# STM32F407_MCU.net
KiCad netlist of a schematic drawn in Altium Designer
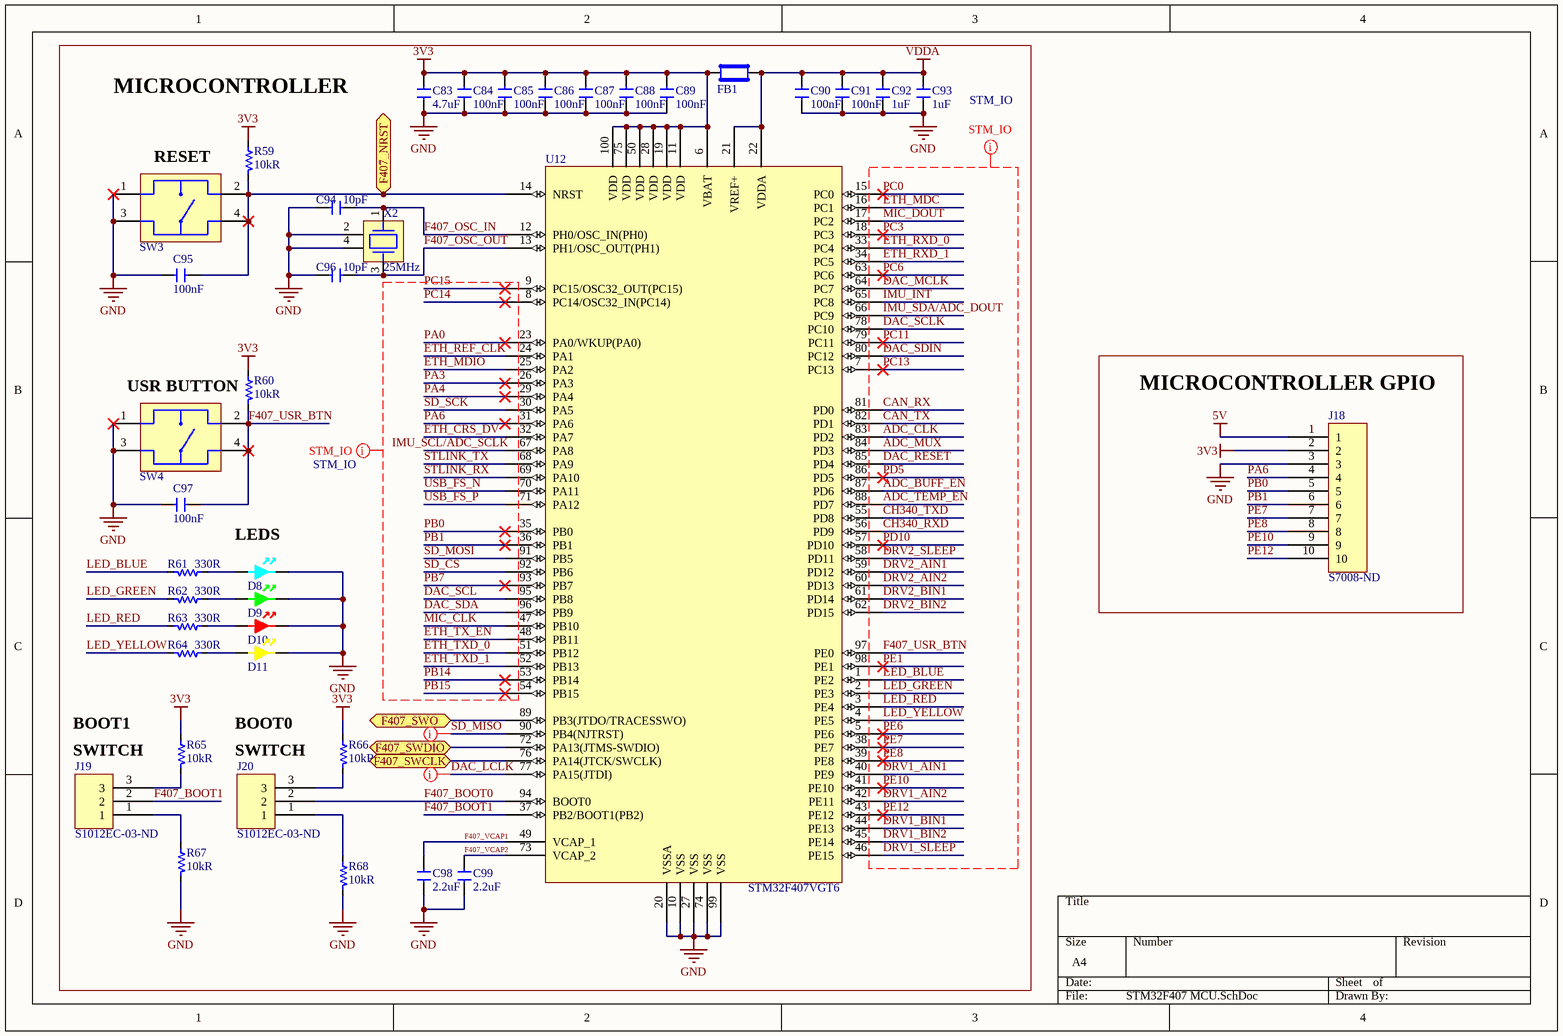
[diagram p0: STM32F407 MCU.SchDoc]

(export (version "E")
  (design (tool "Eeschema 10.0.6"))
  (components
    (comp (ref "C83")
      (value "CAP_4.7uF_%10_0805_25V_X7R_CER")
      (footprint "0805_CAP")
      (description "Cap 4.7UF 25VDC X7R 10% SMD 0805 Embossed Tape")
      (fields
        (field (name "MANUFACTURER") "Murata")
        (field (name "MANUFACTURER PART NUMBER") "GRM21BZ71E475KE15L")
        (field (name "CAPACITANCE") "4.7uF")
      )
      (libsource (lib "Main Schematic Library") (part "CAP_4.7uF_%10_0805_25V_X7R_CER"))
    )
    (comp (ref "C84")
      (value "CAP_0.1uF_%20_50V_0805_X7R_CER")
      (footprint "0805_CAP")
      (description "Cap Ceramic 0.1uF 50V X7R 20% SMD 0805 125C Paper T/R")
      (fields
        (field (name "MANUFACTURER") "KEMET")
        (field (name "MANUFACTURER PART NUMBER") "C0805C104M5RACTU")
        (field (name "CAPACITANCE") "100nF")
      )
      (libsource (lib "Main Schematic Library") (part "CAP_0.1uF_%20_50V_0805_X7R_CER"))
    )
    (comp (ref "C85")
      (value "CAP_0.1uF_%20_50V_0805_X7R_CER")
      (footprint "0805_CAP")
      (description "Cap Ceramic 0.1uF 50V X7R 20% SMD 0805 125C Paper T/R")
      (fields
        (field (name "MANUFACTURER") "KEMET")
        (field (name "MANUFACTURER PART NUMBER") "C0805C104M5RACTU")
        (field (name "CAPACITANCE") "100nF")
      )
      (libsource (lib "Main Schematic Library") (part "CAP_0.1uF_%20_50V_0805_X7R_CER"))
    )
    (comp (ref "C86")
      (value "CAP_0.1uF_%20_50V_0805_X7R_CER")
      (footprint "0805_CAP")
      (description "Cap Ceramic 0.1uF 50V X7R 20% SMD 0805 125C Paper T/R")
      (fields
        (field (name "MANUFACTURER") "KEMET")
        (field (name "MANUFACTURER PART NUMBER") "C0805C104M5RACTU")
        (field (name "CAPACITANCE") "100nF")
      )
      (libsource (lib "Main Schematic Library") (part "CAP_0.1uF_%20_50V_0805_X7R_CER"))
    )
    (comp (ref "C87")
      (value "CAP_0.1uF_%20_50V_0805_X7R_CER")
      (footprint "0805_CAP")
      (description "Cap Ceramic 0.1uF 50V X7R 20% SMD 0805 125C Paper T/R")
      (fields
        (field (name "MANUFACTURER") "KEMET")
        (field (name "MANUFACTURER PART NUMBER") "C0805C104M5RACTU")
        (field (name "CAPACITANCE") "100nF")
      )
      (libsource (lib "Main Schematic Library") (part "CAP_0.1uF_%20_50V_0805_X7R_CER"))
    )
    (comp (ref "C88")
      (value "CAP_0.1uF_%20_50V_0805_X7R_CER")
      (footprint "0805_CAP")
      (description "Cap Ceramic 0.1uF 50V X7R 20% SMD 0805 125C Paper T/R")
      (fields
        (field (name "MANUFACTURER") "KEMET")
        (field (name "MANUFACTURER PART NUMBER") "C0805C104M5RACTU")
        (field (name "CAPACITANCE") "100nF")
      )
      (libsource (lib "Main Schematic Library") (part "CAP_0.1uF_%20_50V_0805_X7R_CER"))
    )
    (comp (ref "C89")
      (value "CAP_0.1uF_%20_50V_0805_X7R_CER")
      (footprint "0805_CAP")
      (description "Cap Ceramic 0.1uF 50V X7R 20% SMD 0805 125C Paper T/R")
      (fields
        (field (name "MANUFACTURER") "KEMET")
        (field (name "MANUFACTURER PART NUMBER") "C0805C104M5RACTU")
        (field (name "CAPACITANCE") "100nF")
      )
      (libsource (lib "Main Schematic Library") (part "CAP_0.1uF_%20_50V_0805_X7R_CER"))
    )
    (comp (ref "C90")
      (value "CAP_0.1uF_%20_50V_0805_X7R_CER")
      (footprint "0805_CAP")
      (description "Cap Ceramic 0.1uF 50V X7R 20% SMD 0805 125C Paper T/R")
      (fields
        (field (name "MANUFACTURER") "KEMET")
        (field (name "MANUFACTURER PART NUMBER") "C0805C104M5RACTU")
        (field (name "CAPACITANCE") "100nF")
      )
      (libsource (lib "Main Schematic Library") (part "CAP_0.1uF_%20_50V_0805_X7R_CER"))
    )
    (comp (ref "C91")
      (value "CAP_0.1uF_%20_50V_0805_X7R_CER")
      (footprint "0805_CAP")
      (description "Cap Ceramic 0.1uF 50V X7R 20% SMD 0805 125C Paper T/R")
      (fields
        (field (name "MANUFACTURER") "KEMET")
        (field (name "MANUFACTURER PART NUMBER") "C0805C104M5RACTU")
        (field (name "CAPACITANCE") "100nF")
      )
      (libsource (lib "Main Schematic Library") (part "CAP_0.1uF_%20_50V_0805_X7R_CER"))
    )
    (comp (ref "C92")
      (value "1uF")
      (footprint "0805_CAP")
      (description "陶瓷电容 1uF(105) 1uF ±10% 25V 0805")
      (fields
        (field (name "MANUFACTURER") "Samsung")
        (field (name "MANUFACTURER PART NUMBER") "CL21B105KAFNNNG")
      )
      (libsource (lib "Main Schematic Library") (part "CAP_1uF_%10_25V_0805_X7R_CER"))
    )
    (comp (ref "C93")
      (value "1uF")
      (footprint "0805_CAP")
      (description "陶瓷电容 1uF(105) 1uF ±10% 25V 0805")
      (fields
        (field (name "MANUFACTURER") "Samsung")
        (field (name "MANUFACTURER PART NUMBER") "CL21B105KAFNNNG")
      )
      (libsource (lib "Main Schematic Library") (part "CAP_1uF_%10_25V_0805_X7R_CER"))
    )
    (comp (ref "C94")
      (value "CAP_10pF_%10_0805_50V_C0G/NPO_CER")
      (footprint "0805_CAP")
      (description "Surface Mount Ceramic Multilayer Capacitor 10pF 10% C0G 50V 0805 Paper T/R")
      (fields
        (field (name "MANUFACTURER") "Yageo")
        (field (name "MANUFACTURER PART NUMBER") "CC0805KRNPO9BN100")
        (field (name "CAPACITANCE") "10pF")
      )
      (libsource (lib "Main Schematic Library") (part "CAP_10pF_%10_0805_50V_C0G/NPO_CER"))
    )
    (comp (ref "C95")
      (value "CAP_100nF_50V_0805_C0G_CER")
      (footprint "0805_CAP")
      (description "Cap Ceramic 0.1uF 50V X7R 20% SMD 0805 125C Paper T/R")
      (fields
        (field (name "MANUFACTURER") "KEMET")
        (field (name "MANUFACTURER PART NUMBER") "C0805C104M5RACTU")
        (field (name "CAPACITANCE") "100nF")
      )
      (libsource (lib "Main Schematic Library") (part "CAP_100nF_50V_0805_C0G_CER"))
    )
    (comp (ref "C96")
      (value "CAP_10pF_%10_0805_50V_C0G/NPO_CER")
      (footprint "0805_CAP")
      (description "Surface Mount Ceramic Multilayer Capacitor 10pF 10% C0G 50V 0805 Paper T/R")
      (fields
        (field (name "MANUFACTURER") "Yageo")
        (field (name "MANUFACTURER PART NUMBER") "CC0805KRNPO9BN100")
        (field (name "CAPACITANCE") "10pF")
      )
      (libsource (lib "Main Schematic Library") (part "CAP_10pF_%10_0805_50V_C0G/NPO_CER"))
    )
    (comp (ref "C97")
      (value "CAP_100nF_50V_0805_C0G_CER")
      (footprint "0805_CAP")
      (description "Cap Ceramic 0.1uF 50V X7R 20% SMD 0805 125C Paper T/R")
      (fields
        (field (name "MANUFACTURER") "KEMET")
        (field (name "MANUFACTURER PART NUMBER") "C0805C104M5RACTU")
        (field (name "CAPACITANCE") "100nF")
      )
      (libsource (lib "Main Schematic Library") (part "CAP_100nF_50V_0805_C0G_CER"))
    )
    (comp (ref "C98")
      (value "2.2uF")
      (footprint "0805_CAP")
      (description "CAP CER 2.2UF 25V X5R 0805")
      (fields
        (field (name "MANUFACTURER") "Samsung")
        (field (name "MANUFACTURER PART NUMBER") "CL21A225KAFNNNE")
      )
      (libsource (lib "Main Schematic Library") (part "CAP_2.2uF_%10_25V_0805_X5R_CER"))
    )
    (comp (ref "C99")
      (value "2.2uF")
      (footprint "0805_CAP")
      (description "CAP CER 2.2UF 25V X5R 0805")
      (fields
        (field (name "MANUFACTURER") "Samsung")
        (field (name "MANUFACTURER PART NUMBER") "CL21A225KAFNNNE")
      )
      (libsource (lib "Main Schematic Library") (part "CAP_2.2uF_%10_25V_0805_X5R_CER"))
    )
    (comp (ref "D8")
      (value "Blue")
      (footprint "DIOC2114X07N-0805-LED-BLUE")
      (description "Blue 0805 140° 112 mcd Clear 3.3 V Surface Mount LED")
      (fields
        (field (name "MANUFACTURER") "Everlight")
        (field (name "MANUFACTURER PART NUMBER") "EAST2012BA2")
      )
      (libsource (lib "Main Schematic Library") (part "LED_BLUE CLEAR_2SMD/0805"))
    )
    (comp (ref "D9")
      (value "Green")
      (footprint "DIOC2114X07N-0805-LED-GREEN")
      (description "Led Green Clear 2SMD")
      (fields
        (field (name "MANUFACTURER") "Everlight")
        (field (name "MANUFACTURER PART NUMBER") "EAST2012GA5")
      )
      (libsource (lib "Main Schematic Library") (part "LED_GREEN CLEAR_2SMD/0805"))
    )
    (comp (ref "D10")
      (value "Red")
      (footprint "DIOC2114X07N-0805-LED-RED")
      (description "Led Red Clear 2SMD")
      (fields
        (field (name "MANUFACTURER") "Everlight")
        (field (name "MANUFACTURER PART NUMBER") "EAST2012RA1")
      )
      (libsource (lib "Main Schematic Library") (part "LED_RED CLEAR_2SMD/0805"))
    )
    (comp (ref "D11")
      (value "Yellow")
      (footprint "DIOC2114X07N-0805-LED-YELLOW")
      (description "Led Yellow Clear 2SMD")
      (fields
        (field (name "MANUFACTURER") "Everlight")
        (field (name "MANUFACTURER PART NUMBER") "EAST2012YA2")
      )
      (libsource (lib "Main Schematic Library") (part "LED_YELLOW CLEAR_2SMD/0805"))
    )
    (comp (ref "FB1")
      (value "FERRITE BEAD_330 OHM_70 mOHM DCR_0805_1LN")
      (footprint "0805_FB")
      (description "0805 330Ω ±25% DCR=0.07Ω 1.5A 应用：电源线")
      (fields (field (name "MANUFACTURER") "Murata") (field (name "TOLERANCE") "25%"))
      (libsource (lib "Main Schematic Library") (part "FERRITE BEAD_330 OHM_70 mOHM DCR_0805_1LN"))
    )
    (comp (ref "J18")
      (value "1x10-Male Header")
      (footprint "DIP_1X10_FEMALE_HEADER_2.54_PITCH")
      (description "10 Position Single Row 2.54 mm Pitch Vertical Through Hole Socket Header")
      (fields
        (field (name "MANUFACTURER") "Sullins")
        (field (name "MANUFACTURER PART NUMBER") "PPTC101LFBN-RC")
        (field (name "SUPPLIER PART NUMBER 1") "S7008-ND")
      )
      (libsource (lib "Main Schematic Library") (part "CONN_1x10_2.54m_Female Header"))
    )
    (comp (ref "J19")
      (value "CONN_1X3_2.54mm_Male Header")
      (footprint "DIP_1X3_MALE_HEADER_2.54_PITCH")
      (description "Conn Header Vert 3POS 2.54MM")
      (fields
        (field (name "MANUFACTURER") "Sullins")
        (field (name "MANUFACTURER PART NUMBER") "PREC003SAAN-RC")
        (field (name "SUPPLIER PART NUMBER 1") "S1012EC-03-ND")
      )
      (libsource (lib "Main Schematic Library") (part "CONN_1X3_2.54mm_Male Header"))
    )
    (comp (ref "J20")
      (value "CONN_1X3_2.54mm_Male Header")
      (footprint "DIP_1X3_MALE_HEADER_2.54_PITCH")
      (description "Conn Header Vert 3POS 2.54MM")
      (fields
        (field (name "MANUFACTURER") "Sullins")
        (field (name "MANUFACTURER PART NUMBER") "PREC003SAAN-RC")
        (field (name "SUPPLIER PART NUMBER 1") "S1012EC-03-ND")
      )
      (libsource (lib "Main Schematic Library") (part "CONN_1X3_2.54mm_Male Header"))
    )
    (comp (ref "R59")
      (value "10k Ohms")
      (footprint "0805_RES")
      (description "Res SMD 0805 10K 1% 0.125W T.C.100PPM")
      (fields
        (field (name "MANUFACTURER") "TDK")
        (field (name "MANUFACTURER PART NUMBER") "C2012X7R1H104K085AA")
        (field (name "RESISTANCE") "10kR")
      )
      (libsource (lib "Main Schematic Library") (part "RES_10K OHM_%1_0805_1/8W"))
    )
    (comp (ref "R60")
      (value "10k Ohms")
      (footprint "0805_RES")
      (description "Res SMD 0805 10K 1% 0.125W T.C.100PPM")
      (fields
        (field (name "MANUFACTURER") "TDK")
        (field (name "MANUFACTURER PART NUMBER") "C2012X7R1H104K085AA")
        (field (name "RESISTANCE") "10kR")
      )
      (libsource (lib "Main Schematic Library") (part "RES_10K OHM_%1_0805_1/8W"))
    )
    (comp (ref "R61")
      (value "RES_330 OHM_5%_0805_1/8W")
      (footprint "0805_RES")
      (description "Res Thick Film 0805 330 Ohm 5% 0.125W(1/8W) ±100ppm/C Pad SMD Automotive T/R")
      (fields
        (field (name "MANUFACTURER") "TE Connectivity")
        (field (name "MANUFACTURER PART NUMBER") "CRGCQ0805J330R")
        (field (name "RESISTANCE") "330R")
      )
      (libsource (lib "Main Schematic Library") (part "RES_330 OHM_5%_0805_1/8W"))
    )
    (comp (ref "R62")
      (value "RES_330 OHM_5%_0805_1/8W")
      (footprint "0805_RES")
      (description "Res Thick Film 0805 330 Ohm 5% 0.125W(1/8W) ±100ppm/C Pad SMD Automotive T/R")
      (fields
        (field (name "MANUFACTURER") "TE Connectivity")
        (field (name "MANUFACTURER PART NUMBER") "CRGCQ0805J330R")
        (field (name "RESISTANCE") "330R")
      )
      (libsource (lib "Main Schematic Library") (part "RES_330 OHM_5%_0805_1/8W"))
    )
    (comp (ref "R63")
      (value "RES_330 OHM_5%_0805_1/8W")
      (footprint "0805_RES")
      (description "Res Thick Film 0805 330 Ohm 5% 0.125W(1/8W) ±100ppm/C Pad SMD Automotive T/R")
      (fields
        (field (name "MANUFACTURER") "TE Connectivity")
        (field (name "MANUFACTURER PART NUMBER") "CRGCQ0805J330R")
        (field (name "RESISTANCE") "330R")
      )
      (libsource (lib "Main Schematic Library") (part "RES_330 OHM_5%_0805_1/8W"))
    )
    (comp (ref "R64")
      (value "RES_330 OHM_5%_0805_1/8W")
      (footprint "0805_RES")
      (description "Res Thick Film 0805 330 Ohm 5% 0.125W(1/8W) ±100ppm/C Pad SMD Automotive T/R")
      (fields
        (field (name "MANUFACTURER") "TE Connectivity")
        (field (name "MANUFACTURER PART NUMBER") "CRGCQ0805J330R")
        (field (name "RESISTANCE") "330R")
      )
      (libsource (lib "Main Schematic Library") (part "RES_330 OHM_5%_0805_1/8W"))
    )
    (comp (ref "R65")
      (value "10k Ohms")
      (footprint "0805_RES")
      (description "Res SMD 0805 10K 1% 0.125W T.C.100PPM")
      (fields
        (field (name "MANUFACTURER") "TDK")
        (field (name "MANUFACTURER PART NUMBER") "C2012X7R1H104K085AA")
        (field (name "RESISTANCE") "10kR")
      )
      (libsource (lib "Main Schematic Library") (part "RES_10K OHM_%1_0805_1/8W"))
    )
    (comp (ref "R66")
      (value "10k Ohms")
      (footprint "0805_RES")
      (description "Res SMD 0805 10K 1% 0.125W T.C.100PPM")
      (fields
        (field (name "MANUFACTURER") "TDK")
        (field (name "MANUFACTURER PART NUMBER") "C2012X7R1H104K085AA")
        (field (name "RESISTANCE") "10kR")
      )
      (libsource (lib "Main Schematic Library") (part "RES_10K OHM_%1_0805_1/8W"))
    )
    (comp (ref "R67")
      (value "10k Ohms")
      (footprint "0805_RES")
      (description "Res SMD 0805 10K 1% 0.125W T.C.100PPM")
      (fields
        (field (name "MANUFACTURER") "TDK")
        (field (name "MANUFACTURER PART NUMBER") "C2012X7R1H104K085AA")
        (field (name "RESISTANCE") "10kR")
      )
      (libsource (lib "Main Schematic Library") (part "RES_10K OHM_%1_0805_1/8W"))
    )
    (comp (ref "R68")
      (value "10k Ohms")
      (footprint "0805_RES")
      (description "Res SMD 0805 10K 1% 0.125W T.C.100PPM")
      (fields
        (field (name "MANUFACTURER") "TDK")
        (field (name "MANUFACTURER PART NUMBER") "C2012X7R1H104K085AA")
        (field (name "RESISTANCE") "10kR")
      )
      (libsource (lib "Main Schematic Library") (part "RES_10K OHM_%1_0805_1/8W"))
    )
    (comp (ref "SW3")
      (value "SWITCH_TACTILE_SPST-NO_0.05A_12V")
      (footprint "TACT_SWITCH_6MMX6MM")
      (description "Switch Tactile N.O. SPST Round Button Gull Wing 0.05A 12VDC 100000Cycles 1.27N SMD T/R")
      (fields
        (field (name "MANUFACTURER") "ITT C&K")
        (field (name "MANUFACTURER PART NUMBER") "PTS645SL43SMTR92LFS")
      )
      (libsource (lib "Main Schematic Library") (part "SWITCH_TACTILE_SPST-NO_0.05A_12V"))
    )
    (comp (ref "SW4")
      (value "SWITCH_TACTILE_SPST-NO_0.05A_12V")
      (footprint "TACT_SWITCH_6MMX6MM")
      (description "Switch Tactile N.O. SPST Round Button Gull Wing 0.05A 12VDC 100000Cycles 1.27N SMD T/R")
      (fields
        (field (name "MANUFACTURER") "ITT C&K")
        (field (name "MANUFACTURER PART NUMBER") "PTS645SL43SMTR92LFS")
      )
      (libsource (lib "Main Schematic Library") (part "SWITCH_TACTILE_SPST-NO_0.05A_12V"))
    )
    (comp (ref "U12")
      (value "STM32F407VGT6")
      (footprint "STM32F407_LQFP50P1600X1600X160-100N")
      (description "MCU 32-bit STM32F ARM Cortex M4F RISC 1024KB Flash 2.5V/3.3V 100-Pin LQFP Tray")
      (fields (field (name "MANUFACTURER") "STMicroelectronics"))
      (libsource (lib "Main Schematic Library") (part "IC_MCU_STM32F407VGT6"))
    )
    (comp (ref "X2")
      (value "25MHz")
      (footprint "4-SMD-ABM8G-25.000MHZ-4Y-T3")
      (description "Crystal 25MHz ±30ppm (Tol) ±30ppm (Stability) 10pF FUND 60Ohm 4-Pin Ultra Mini-CSMD T/R")
      (fields
        (field (name "MANUFACTURER") "Abracon")
        (field (name "MANUFACTURER PART NUMBER") "ABM8G-25.000MHZ-4Y-T3")
      )
      (libsource (lib "Main Schematic Library") (part "CRYSTAL_25.0000MHZ_10PF_SMD"))
    )
  )
  (nets
    (net (code "1") (name "/ADC_BUFF_EN") (class "Default")
      (node (ref "U12") (pin "87") (pinfunction "PD6_87") (pintype "bidirectional"))
    )
    (net (code "2") (name "/ADC_CLK") (class "Default")
      (node (ref "U12") (pin "83") (pinfunction "PD2_83") (pintype "bidirectional"))
    )
    (net (code "3") (name "/ADC_MUX") (class "Default")
      (node (ref "U12") (pin "84") (pinfunction "PD3_84") (pintype "bidirectional"))
    )
    (net (code "4") (name "/ADC_TEMP_EN") (class "Default")
      (node (ref "U12") (pin "88") (pinfunction "PD7_88") (pintype "bidirectional"))
    )
    (net (code "5") (name "/CAN_RX") (class "Default")
      (node (ref "U12") (pin "81") (pinfunction "PD0_81") (pintype "bidirectional"))
    )
    (net (code "6") (name "/CAN_TX") (class "Default")
      (node (ref "U12") (pin "82") (pinfunction "PD1_82") (pintype "bidirectional"))
    )
    (net (code "7") (name "/CH340_RXD") (class "Default")
      (node (ref "U12") (pin "56") (pinfunction "PD9_56") (pintype "bidirectional"))
    )
    (net (code "8") (name "/CH340_TXD") (class "Default")
      (node (ref "U12") (pin "55") (pinfunction "PD8_55") (pintype "bidirectional"))
    )
    (net (code "9") (name "/DAC_LCLK") (class "Default")
      (node (ref "U12") (pin "77") (pinfunction "PA15(JTDI)_77") (pintype "bidirectional"))
    )
    (net (code "10") (name "/DAC_MCLK") (class "Default")
      (node (ref "U12") (pin "64") (pinfunction "PC7_64") (pintype "bidirectional"))
    )
    (net (code "11") (name "/DAC_RESET") (class "Default")
      (node (ref "U12") (pin "85") (pinfunction "PD4_85") (pintype "bidirectional"))
    )
    (net (code "12") (name "/DAC_SCL") (class "Default")
      (node (ref "U12") (pin "95") (pinfunction "PB8_95") (pintype "bidirectional"))
    )
    (net (code "13") (name "/DAC_SCLK") (class "Default")
      (node (ref "U12") (pin "78") (pinfunction "PC10_78") (pintype "bidirectional"))
    )
    (net (code "14") (name "/DAC_SDA") (class "Default")
      (node (ref "U12") (pin "96") (pinfunction "PB9_96") (pintype "bidirectional"))
    )
    (net (code "15") (name "/DAC_SDIN") (class "Default")
      (node (ref "U12") (pin "80") (pinfunction "PC12_80") (pintype "bidirectional"))
    )
    (net (code "16") (name "/DRV1_AIN1") (class "Default")
      (node (ref "U12") (pin "40") (pinfunction "PE9_40") (pintype "bidirectional"))
    )
    (net (code "17") (name "/DRV1_AIN2") (class "Default")
      (node (ref "U12") (pin "42") (pinfunction "PE11_42") (pintype "bidirectional"))
    )
    (net (code "18") (name "/DRV1_BIN1") (class "Default")
      (node (ref "U12") (pin "44") (pinfunction "PE13_44") (pintype "bidirectional"))
    )
    (net (code "19") (name "/DRV1_BIN2") (class "Default")
      (node (ref "U12") (pin "45") (pinfunction "PE14_45") (pintype "bidirectional"))
    )
    (net (code "20") (name "/DRV1_SLEEP") (class "Default")
      (node (ref "U12") (pin "46") (pinfunction "PE15_46") (pintype "bidirectional"))
    )
    (net (code "21") (name "/DRV2_AIN1") (class "Default")
      (node (ref "U12") (pin "59") (pinfunction "PD12_59") (pintype "bidirectional"))
    )
    (net (code "22") (name "/DRV2_AIN2") (class "Default")
      (node (ref "U12") (pin "60") (pinfunction "PD13_60") (pintype "bidirectional"))
    )
    (net (code "23") (name "/DRV2_BIN1") (class "Default")
      (node (ref "U12") (pin "61") (pinfunction "PD14_61") (pintype "bidirectional"))
    )
    (net (code "24") (name "/DRV2_BIN2") (class "Default")
      (node (ref "U12") (pin "62") (pinfunction "PD15_62") (pintype "bidirectional"))
    )
    (net (code "25") (name "/DRV2_SLEEP") (class "Default")
      (node (ref "U12") (pin "58") (pinfunction "PD11_58") (pintype "bidirectional"))
    )
    (net (code "26") (name "/ETH_CRS_DV") (class "Default")
      (node (ref "U12") (pin "32") (pinfunction "PA7_32") (pintype "bidirectional"))
    )
    (net (code "27") (name "/ETH_MDC") (class "Default")
      (node (ref "U12") (pin "16") (pinfunction "PC1_16") (pintype "bidirectional"))
    )
    (net (code "28") (name "/ETH_MDIO") (class "Default")
      (node (ref "U12") (pin "25") (pinfunction "PA2_25") (pintype "bidirectional"))
    )
    (net (code "29") (name "/ETH_REF_CLK") (class "Default")
      (node (ref "U12") (pin "24") (pinfunction "PA1_24") (pintype "bidirectional"))
    )
    (net (code "30") (name "/ETH_RXD_0") (class "Default")
      (node (ref "U12") (pin "33") (pinfunction "PC4_33") (pintype "bidirectional"))
    )
    (net (code "31") (name "/ETH_RXD_1") (class "Default")
      (node (ref "U12") (pin "34") (pinfunction "PC5_34") (pintype "bidirectional"))
    )
    (net (code "32") (name "/ETH_TXD_0") (class "Default")
      (node (ref "U12") (pin "51") (pinfunction "PB12_51") (pintype "bidirectional"))
    )
    (net (code "33") (name "/ETH_TXD_1") (class "Default")
      (node (ref "U12") (pin "52") (pinfunction "PB13_52") (pintype "bidirectional"))
    )
    (net (code "34") (name "/ETH_TX_EN") (class "Default")
      (node (ref "U12") (pin "48") (pinfunction "PB11_48") (pintype "bidirectional"))
    )
    (net (code "35") (name "/F407_BOOT0") (class "Default")
      (node (ref "J20") (pin "2") (pinfunction "2_2") (pintype "passive"))
      (node (ref "U12") (pin "94") (pinfunction "BOOT0_94") (pintype "bidirectional"))
    )
    (net (code "36") (name "/F407_BOOT1") (class "Default")
      (node (ref "J19") (pin "2") (pinfunction "2_2") (pintype "passive"))
      (node (ref "U12") (pin "37") (pinfunction "PB2/BOOT1(PB2)_37") (pintype "bidirectional"))
    )
    (net (code "37") (name "/F407_NRST") (class "Default")
      (node (ref "C95") (pin "1") (pinfunction "1_1") (pintype "passive"))
      (node (ref "R59") (pin "1") (pinfunction "1_1") (pintype "passive"))
      (node (ref "SW3") (pin "2") (pinfunction "2_2") (pintype "passive"))
      (node (ref "SW3") (pin "4") (pinfunction "4_4") (pintype "passive"))
      (node (ref "U12") (pin "14") (pinfunction "NRST_14") (pintype "bidirectional"))
    )
    (net (code "38") (name "/F407_OSC_IN") (class "Default")
      (node (ref "C94") (pin "2") (pinfunction "2_2") (pintype "passive"))
      (node (ref "U12") (pin "12") (pinfunction "PH0/OSC_IN(PH0)_12") (pintype "bidirectional"))
      (node (ref "X2") (pin "1") (pinfunction "1_1") (pintype "passive"))
    )
    (net (code "39") (name "/F407_OSC_OUT") (class "Default")
      (node (ref "C96") (pin "2") (pinfunction "2_2") (pintype "passive"))
      (node (ref "U12") (pin "13") (pinfunction "PH1/OSC_OUT(PH1)_13") (pintype "bidirectional"))
      (node (ref "X2") (pin "3") (pinfunction "3_3") (pintype "passive"))
    )
    (net (code "40") (name "/F407_SWCLK") (class "Default")
      (node (ref "U12") (pin "76") (pinfunction "PA14(JTCK/SWCLK)_76") (pintype "bidirectional"))
    )
    (net (code "41") (name "/F407_SWDIO") (class "Default")
      (node (ref "U12") (pin "72") (pinfunction "PA13(JTMS-SWDIO)_72") (pintype "bidirectional"))
    )
    (net (code "42") (name "/F407_SWO") (class "Default")
      (node (ref "U12") (pin "89") (pinfunction "PB3(JTDO/TRACESSWO)_89") (pintype "bidirectional"))
    )
    (net (code "43") (name "/F407_USR_BTN") (class "Default")
      (node (ref "C97") (pin "1") (pinfunction "1_1") (pintype "passive"))
      (node (ref "R60") (pin "1") (pinfunction "1_1") (pintype "passive"))
      (node (ref "SW4") (pin "2") (pinfunction "2_2") (pintype "passive"))
      (node (ref "SW4") (pin "4") (pinfunction "4_4") (pintype "passive"))
      (node (ref "U12") (pin "97") (pinfunction "PE0_97") (pintype "bidirectional"))
    )
    (net (code "44") (name "/F407_VCAP1") (class "Default")
      (node (ref "C98") (pin "2") (pinfunction "2_2") (pintype "passive"))
      (node (ref "U12") (pin "49") (pinfunction "VCAP_1_49") (pintype "power_in"))
    )
    (net (code "45") (name "/F407_VCAP2") (class "Default")
      (node (ref "C99") (pin "2") (pinfunction "2_2") (pintype "passive"))
      (node (ref "U12") (pin "73") (pinfunction "VCAP_2_73") (pintype "power_in"))
    )
    (net (code "46") (name "/IMU_INT") (class "Default")
      (node (ref "U12") (pin "65") (pinfunction "PC8_65") (pintype "bidirectional"))
    )
    (net (code "47") (name "/IMU_SCL{slash}ADC_SCLK") (class "Default")
      (node (ref "U12") (pin "67") (pinfunction "PA8_67") (pintype "bidirectional"))
    )
    (net (code "48") (name "/IMU_SDA{slash}ADC_DOUT") (class "Default")
      (node (ref "U12") (pin "66") (pinfunction "PC9_66") (pintype "bidirectional"))
    )
    (net (code "49") (name "/LED_BLUE") (class "Default")
      (node (ref "R61") (pin "1") (pinfunction "1_1") (pintype "passive"))
      (node (ref "U12") (pin "1") (pinfunction "PE2_1") (pintype "bidirectional"))
    )
    (net (code "50") (name "/LED_GREEN") (class "Default")
      (node (ref "R62") (pin "1") (pinfunction "1_1") (pintype "passive"))
      (node (ref "U12") (pin "2") (pinfunction "PE3_2") (pintype "bidirectional"))
    )
    (net (code "51") (name "/LED_RED") (class "Default")
      (node (ref "R63") (pin "1") (pinfunction "1_1") (pintype "passive"))
      (node (ref "U12") (pin "3") (pinfunction "PE4_3") (pintype "bidirectional"))
    )
    (net (code "52") (name "/LED_YELLOW") (class "Default")
      (node (ref "R64") (pin "1") (pinfunction "1_1") (pintype "passive"))
      (node (ref "U12") (pin "4") (pinfunction "PE5_4") (pintype "bidirectional"))
    )
    (net (code "53") (name "/MIC_CLK") (class "Default")
      (node (ref "U12") (pin "47") (pinfunction "PB10_47") (pintype "bidirectional"))
    )
    (net (code "54") (name "/MIC_DOUT") (class "Default")
      (node (ref "U12") (pin "17") (pinfunction "PC2_17") (pintype "bidirectional"))
    )
    (net (code "55") (name "/PA0") (class "Default")
      (node (ref "U12") (pin "23") (pinfunction "PA0/WKUP(PA0)_23") (pintype "bidirectional+no_connect"))
    )
    (net (code "56") (name "/PA3") (class "Default")
      (node (ref "U12") (pin "26") (pinfunction "PA3_26") (pintype "bidirectional+no_connect"))
    )
    (net (code "57") (name "/PA4") (class "Default")
      (node (ref "U12") (pin "29") (pinfunction "PA4_29") (pintype "bidirectional+no_connect"))
    )
    (net (code "58") (name "/PA6") (class "Default")
      (node (ref "J18") (pin "4") (pinfunction "4_4") (pintype "passive"))
      (node (ref "U12") (pin "31") (pinfunction "PA6_31") (pintype "bidirectional"))
    )
    (net (code "59") (name "/PB0") (class "Default")
      (node (ref "J18") (pin "5") (pinfunction "5_5") (pintype "passive"))
      (node (ref "U12") (pin "35") (pinfunction "PB0_35") (pintype "bidirectional"))
    )
    (net (code "60") (name "/PB1") (class "Default")
      (node (ref "J18") (pin "6") (pinfunction "6_6") (pintype "passive"))
      (node (ref "U12") (pin "36") (pinfunction "PB1_36") (pintype "bidirectional"))
    )
    (net (code "61") (name "/PB7") (class "Default")
      (node (ref "U12") (pin "93") (pinfunction "PB7_93") (pintype "bidirectional+no_connect"))
    )
    (net (code "62") (name "/PB14") (class "Default")
      (node (ref "U12") (pin "53") (pinfunction "PB14_53") (pintype "bidirectional+no_connect"))
    )
    (net (code "63") (name "/PB15") (class "Default")
      (node (ref "U12") (pin "54") (pinfunction "PB15_54") (pintype "bidirectional+no_connect"))
    )
    (net (code "64") (name "/PC0") (class "Default")
      (node (ref "U12") (pin "15") (pinfunction "PC0_15") (pintype "bidirectional+no_connect"))
    )
    (net (code "65") (name "/PC3") (class "Default")
      (node (ref "U12") (pin "18") (pinfunction "PC3_18") (pintype "bidirectional+no_connect"))
    )
    (net (code "66") (name "/PC6") (class "Default")
      (node (ref "U12") (pin "63") (pinfunction "PC6_63") (pintype "bidirectional+no_connect"))
    )
    (net (code "67") (name "/PC11") (class "Default")
      (node (ref "U12") (pin "79") (pinfunction "PC11_79") (pintype "bidirectional+no_connect"))
    )
    (net (code "68") (name "/PC13") (class "Default")
      (node (ref "U12") (pin "7") (pinfunction "PC13_7") (pintype "bidirectional+no_connect"))
    )
    (net (code "69") (name "/PC14") (class "Default")
      (node (ref "U12") (pin "8") (pinfunction "PC14/OSC32_IN(PC14)_8") (pintype "bidirectional+no_connect"))
    )
    (net (code "70") (name "/PC15") (class "Default")
      (node (ref "U12") (pin "9") (pinfunction "PC15/OSC32_OUT(PC15)_9") (pintype "bidirectional+no_connect"))
    )
    (net (code "71") (name "/PD5") (class "Default")
      (node (ref "U12") (pin "86") (pinfunction "PD5_86") (pintype "bidirectional+no_connect"))
    )
    (net (code "72") (name "/PD10") (class "Default")
      (node (ref "U12") (pin "57") (pinfunction "PD10_57") (pintype "bidirectional+no_connect"))
    )
    (net (code "73") (name "/PE1") (class "Default")
      (node (ref "U12") (pin "98") (pinfunction "PE1_98") (pintype "bidirectional+no_connect"))
    )
    (net (code "74") (name "/PE6") (class "Default")
      (node (ref "U12") (pin "5") (pinfunction "PE6_5") (pintype "bidirectional+no_connect"))
    )
    (net (code "75") (name "/PE7") (class "Default")
      (node (ref "J18") (pin "7") (pinfunction "7_7") (pintype "passive"))
      (node (ref "U12") (pin "38") (pinfunction "PE7_38") (pintype "bidirectional"))
    )
    (net (code "76") (name "/PE8") (class "Default")
      (node (ref "J18") (pin "8") (pinfunction "8_8") (pintype "passive"))
      (node (ref "U12") (pin "39") (pinfunction "PE8_39") (pintype "bidirectional"))
    )
    (net (code "77") (name "/PE10") (class "Default")
      (node (ref "J18") (pin "9") (pinfunction "9_9") (pintype "passive"))
      (node (ref "U12") (pin "41") (pinfunction "PE10_41") (pintype "bidirectional"))
    )
    (net (code "78") (name "/PE12") (class "Default")
      (node (ref "J18") (pin "10") (pinfunction "10_10") (pintype "passive"))
      (node (ref "U12") (pin "43") (pinfunction "PE12_43") (pintype "bidirectional"))
    )
    (net (code "79") (name "/SD_CS") (class "Default")
      (node (ref "U12") (pin "92") (pinfunction "PB6_92") (pintype "bidirectional"))
    )
    (net (code "80") (name "/SD_MISO") (class "Default")
      (node (ref "U12") (pin "90") (pinfunction "PB4(NJTRST)_90") (pintype "bidirectional"))
    )
    (net (code "81") (name "/SD_MOSI") (class "Default")
      (node (ref "U12") (pin "91") (pinfunction "PB5_91") (pintype "bidirectional"))
    )
    (net (code "82") (name "/SD_SCK") (class "Default")
      (node (ref "U12") (pin "30") (pinfunction "PA5_30") (pintype "bidirectional"))
    )
    (net (code "83") (name "/STLINK_RX") (class "Default")
      (node (ref "U12") (pin "69") (pinfunction "PA10_69") (pintype "bidirectional"))
    )
    (net (code "84") (name "/STLINK_TX") (class "Default")
      (node (ref "U12") (pin "68") (pinfunction "PA9_68") (pintype "bidirectional"))
    )
    (net (code "85") (name "/USB_FS_N") (class "Default")
      (node (ref "U12") (pin "70") (pinfunction "PA11_70") (pintype "bidirectional"))
    )
    (net (code "86") (name "/USB_FS_P") (class "Default")
      (node (ref "U12") (pin "71") (pinfunction "PA12_71") (pintype "bidirectional"))
    )
    (net (code "87") (name "3V3") (class "Default")
      (node (ref "C83") (pin "2") (pinfunction "2_2") (pintype "passive"))
      (node (ref "C84") (pin "2") (pinfunction "2_2") (pintype "passive"))
      (node (ref "C85") (pin "2") (pinfunction "2_2") (pintype "passive"))
      (node (ref "C86") (pin "2") (pinfunction "2_2") (pintype "passive"))
      (node (ref "C87") (pin "2") (pinfunction "2_2") (pintype "passive"))
      (node (ref "C88") (pin "2") (pinfunction "2_2") (pintype "passive"))
      (node (ref "C89") (pin "2") (pinfunction "2_2") (pintype "passive"))
      (node (ref "FB1") (pin "1") (pinfunction "1_1") (pintype "passive"))
      (node (ref "J18") (pin "2") (pinfunction "2_2") (pintype "passive"))
      (node (ref "R59") (pin "2") (pinfunction "2_2") (pintype "passive"))
      (node (ref "R60") (pin "2") (pinfunction "2_2") (pintype "passive"))
      (node (ref "R65") (pin "2") (pinfunction "2_2") (pintype "passive"))
      (node (ref "R66") (pin "2") (pinfunction "2_2") (pintype "passive"))
      (node (ref "U12") (pin "100") (pinfunction "VDD_100") (pintype "power_in"))
      (node (ref "U12") (pin "11") (pinfunction "VDD_11") (pintype "power_in"))
      (node (ref "U12") (pin "19") (pinfunction "VDD_19") (pintype "power_in"))
      (node (ref "U12") (pin "28") (pinfunction "VDD_28") (pintype "power_in"))
      (node (ref "U12") (pin "50") (pinfunction "VDD_50") (pintype "power_in"))
      (node (ref "U12") (pin "6") (pinfunction "VBAT_6") (pintype "power_in"))
      (node (ref "U12") (pin "75") (pinfunction "VDD_75") (pintype "power_in"))
    )
    (net (code "88") (name "5V") (class "Default")
      (node (ref "J18") (pin "1") (pinfunction "1_1") (pintype "passive"))
    )
    (net (code "89") (name "GND") (class "Default")
      (node (ref "C83") (pin "1") (pinfunction "1_1") (pintype "passive"))
      (node (ref "C84") (pin "1") (pinfunction "1_1") (pintype "passive"))
      (node (ref "C85") (pin "1") (pinfunction "1_1") (pintype "passive"))
      (node (ref "C86") (pin "1") (pinfunction "1_1") (pintype "passive"))
      (node (ref "C87") (pin "1") (pinfunction "1_1") (pintype "passive"))
      (node (ref "C88") (pin "1") (pinfunction "1_1") (pintype "passive"))
      (node (ref "C89") (pin "1") (pinfunction "1_1") (pintype "passive"))
      (node (ref "C90") (pin "1") (pinfunction "1_1") (pintype "passive"))
      (node (ref "C91") (pin "1") (pinfunction "1_1") (pintype "passive"))
      (node (ref "C92") (pin "1") (pinfunction "1_1") (pintype "passive"))
      (node (ref "C93") (pin "1") (pinfunction "1_1") (pintype "passive"))
      (node (ref "C94") (pin "1") (pinfunction "1_1") (pintype "passive"))
      (node (ref "C95") (pin "2") (pinfunction "2_2") (pintype "passive"))
      (node (ref "C96") (pin "1") (pinfunction "1_1") (pintype "passive"))
      (node (ref "C97") (pin "2") (pinfunction "2_2") (pintype "passive"))
      (node (ref "C98") (pin "1") (pinfunction "1_1") (pintype "passive"))
      (node (ref "C99") (pin "1") (pinfunction "1_1") (pintype "passive"))
      (node (ref "D10") (pin "1") (pinfunction "CATHODE_1") (pintype "passive"))
      (node (ref "D11") (pin "1") (pinfunction "CATHODE_1") (pintype "passive"))
      (node (ref "D8") (pin "1") (pinfunction "CATHODE_1") (pintype "passive"))
      (node (ref "D9") (pin "1") (pinfunction "CATHODE_1") (pintype "passive"))
      (node (ref "J18") (pin "3") (pinfunction "3_3") (pintype "passive"))
      (node (ref "R67") (pin "1") (pinfunction "1_1") (pintype "passive"))
      (node (ref "R68") (pin "1") (pinfunction "1_1") (pintype "passive"))
      (node (ref "SW3") (pin "1") (pinfunction "1_1") (pintype "passive"))
      (node (ref "SW3") (pin "3") (pinfunction "3_3") (pintype "passive"))
      (node (ref "SW4") (pin "1") (pinfunction "1_1") (pintype "passive"))
      (node (ref "SW4") (pin "3") (pinfunction "3_3") (pintype "passive"))
      (node (ref "U12") (pin "10") (pinfunction "VSS_10") (pintype "power_in"))
      (node (ref "U12") (pin "20") (pinfunction "VSSA_20") (pintype "power_in"))
      (node (ref "U12") (pin "27") (pinfunction "VSS_27") (pintype "power_in"))
      (node (ref "U12") (pin "74") (pinfunction "VSS_74") (pintype "power_in"))
      (node (ref "U12") (pin "99") (pinfunction "VSS_99") (pintype "power_in"))
      (node (ref "X2") (pin "2") (pinfunction "GND_2") (pintype "passive"))
      (node (ref "X2") (pin "4") (pinfunction "GND_4") (pintype "passive"))
    )
    (net (code "90") (name "Net-(D8-ANODE)") (class "Default")
      (node (ref "D8") (pin "2") (pinfunction "ANODE_2") (pintype "passive"))
      (node (ref "R61") (pin "2") (pinfunction "2_2") (pintype "passive"))
    )
    (net (code "91") (name "Net-(D9-ANODE)") (class "Default")
      (node (ref "D9") (pin "2") (pinfunction "ANODE_2") (pintype "passive"))
      (node (ref "R62") (pin "2") (pinfunction "2_2") (pintype "passive"))
    )
    (net (code "92") (name "Net-(D10-ANODE)") (class "Default")
      (node (ref "D10") (pin "2") (pinfunction "ANODE_2") (pintype "passive"))
      (node (ref "R63") (pin "2") (pinfunction "2_2") (pintype "passive"))
    )
    (net (code "93") (name "Net-(D11-ANODE)") (class "Default")
      (node (ref "D11") (pin "2") (pinfunction "ANODE_2") (pintype "passive"))
      (node (ref "R64") (pin "2") (pinfunction "2_2") (pintype "passive"))
    )
    (net (code "94") (name "Net-(J19-Pad1)") (class "Default")
      (node (ref "J19") (pin "1") (pinfunction "1_1") (pintype "passive"))
      (node (ref "R67") (pin "2") (pinfunction "2_2") (pintype "passive"))
    )
    (net (code "95") (name "Net-(J19-Pad3)") (class "Default")
      (node (ref "J19") (pin "3") (pinfunction "3_3") (pintype "passive"))
      (node (ref "R65") (pin "1") (pinfunction "1_1") (pintype "passive"))
    )
    (net (code "96") (name "Net-(J20-Pad1)") (class "Default")
      (node (ref "J20") (pin "1") (pinfunction "1_1") (pintype "passive"))
      (node (ref "R68") (pin "2") (pinfunction "2_2") (pintype "passive"))
    )
    (net (code "97") (name "Net-(J20-Pad3)") (class "Default")
      (node (ref "J20") (pin "3") (pinfunction "3_3") (pintype "passive"))
      (node (ref "R66") (pin "1") (pinfunction "1_1") (pintype "passive"))
    )
    (net (code "98") (name "VDDA") (class "Default")
      (node (ref "C90") (pin "2") (pinfunction "2_2") (pintype "passive"))
      (node (ref "C91") (pin "2") (pinfunction "2_2") (pintype "passive"))
      (node (ref "C92") (pin "2") (pinfunction "2_2") (pintype "passive"))
      (node (ref "C93") (pin "2") (pinfunction "2_2") (pintype "passive"))
      (node (ref "FB1") (pin "2") (pinfunction "2_2") (pintype "passive"))
      (node (ref "U12") (pin "21") (pinfunction "VREF+_21") (pintype "power_in"))
      (node (ref "U12") (pin "22") (pinfunction "VDDA_22") (pintype "power_in"))
    )
  )
)
